# Power.net
KiCad netlist of a schematic drawn in Altium Designer
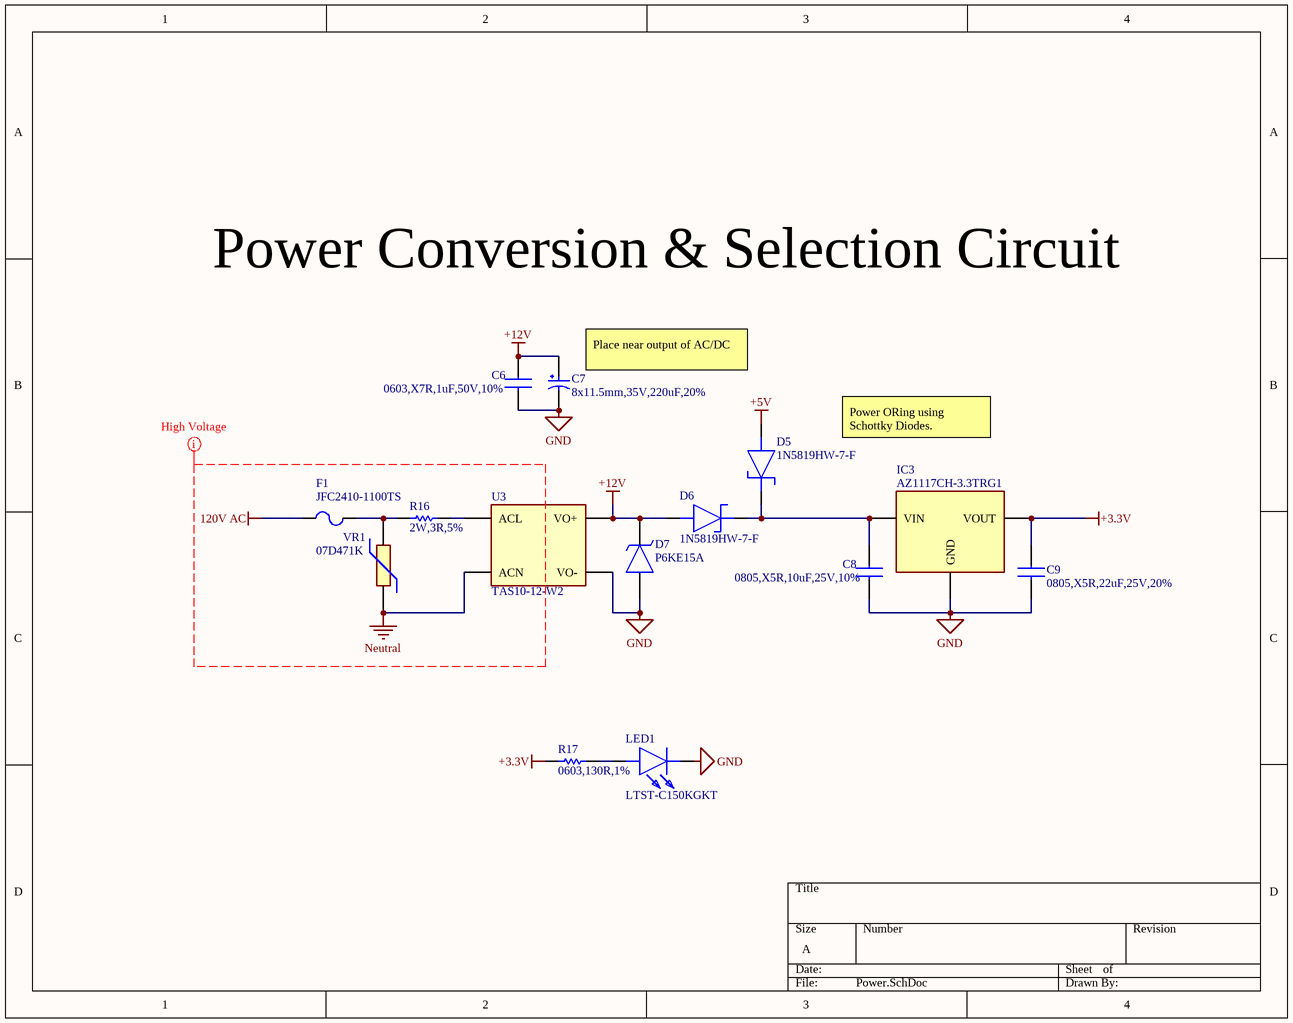
[diagram p0: Power.SchDoc]

(export (version "E")
  (design (tool "Eeschema 10.0.6"))
  (components
    (comp (ref "C6")
      (value "0603,X7R,1uF,50V,10%")
      (footprint "CAPC1608X90N")
      (description "50V 1uF X7R ±10% 0603 Multilayer Ceramic Capacitors MLCC - SMD/SMT ROHS")
      (fields
        (field (name "MANUFACTURER_PART_NUMBER") "CC0603KRX7R9BB105")
        (field (name "MOUSER PART NUMBER") "603-CC603KRX7R9BB105")
      )
      (libsource (lib "LC-SchLib") (part "CC0603KRX7R9BB105"))
    )
    (comp (ref "C7")
      (value "8x11.5mm,35V,220uF,20%")
      (footprint "CAPPRD350W60D825H1350")
      (fields
        (field (name "MANUFACTURER_PART_NUMBER") "35ZLH220MEFC8X11.5")
        (field (name "MOUSER PART NUMBER") "232-35ZLH220MEFC8X15")
        (field (name "LCSC PART NUMBER") "C107639")
      )
      (libsource (lib "LC-SchLib") (part "35ZLH220MEFC8X11.5"))
    )
    (comp (ref "C8")
      (value "0805,X5R,10uF,25V,10%")
      (footprint "CAPC2012X145N")
      (description "10 µF ±10% 25V Ceramic Capacitor X5R 0805 (2012 Metric)")
      (fields
        (field (name "MANUFACTURER_PART_NUMBER") "CC0805KKX5R8BB106")
        (field (name "MOUSER PART NUMBER") "603-CC805KKX5R8BB106")
      )
      (libsource (lib "LC-SchLib") (part "CC0805KKX5R8BB106"))
    )
    (comp (ref "C9")
      (value "0805,X5R,22uF,25V,20%")
      (footprint "CAPC2012X145N")
      (description "22 µF ±20% 25V Ceramic Capacitor X5R 0805 (2012 Metric)")
      (fields
        (field (name "MANUFACTURER_PART_NUMBER") "CC0805MKX5R8BB226")
        (field (name "MOUSER PART NUMBER") "603-CC805MKX5R8BB226")
      )
      (libsource (lib "LC-SchLib") (part "CC0805MKX5R8BB226"))
    )
    (comp (ref "D5")
      (value "1N5819HW-7-F")
      (footprint "SOD3716X145N")
      (description "40V 450mV@1A 1A SOD-123 Schottky Diodes ROHS")
      (fields (field (name "MOUSER PART NUMBER") "621-1N5819HW-F") (field (name "LCSC PART NUMBER") "C82544"))
      (libsource (lib "LC-SchLib") (part "1N5819HW-7-F"))
    )
    (comp (ref "D6")
      (value "1N5819HW-7-F")
      (footprint "SOD3716X145N")
      (description "40V 450mV@1A 1A SOD-123 Schottky Diodes ROHS")
      (fields (field (name "MOUSER PART NUMBER") "621-1N5819HW-F") (field (name "LCSC PART NUMBER") "C82544"))
      (libsource (lib "LC-SchLib") (part "1N5819HW-7-F"))
    )
    (comp (ref "D7")
      (value "P6KE15A")
      (footprint "DIOAD1936W88L640D324")
      (fields (field (name "MOUSER PART NUMBER") "511-P6KE15A") (field (name "LCSC PART NUMBER") "C1974865"))
      (libsource (lib "LC-SchLib") (part "P6KE15A"))
    )
    (comp (ref "F1")
      (value "JFC2410-1100TS")
      (footprint "F2410")
      (description "50A Surface Mount Fuse 1A 250V 250V 2410 Disposable fuses ROHS")
      (fields (field (name "LCSC PART NUMBER") "C136380"))
      (libsource (lib "LC-SchLib") (part "JFC2410-1100TS"))
    )
    (comp (ref "IC3")
      (value "AZ1117CH-3.3TRG1")
      (footprint "SOT230P700X180-4N")
      (fields
        (field (name "MOUSER PART NUMBER") "621-AZ1117CH-3.3TRG1")
        (field (name "LCSC PART NUMBER") "C92102")
      )
      (libsource (lib "LC-SchLib") (part "AZ1117CH-3.3TRG1"))
    )
    (comp (ref "LED1")
      (value "LTST-C150KGKT")
      (footprint "LEDC3216X120N")
      (fields
        (field (name "MOUSER PART NUMBER") "859-LTST-C150KGKT")
        (field (name "LCSC PART NUMBER") "C125085")
      )
      (libsource (lib "LC-SchLib") (part "LTST-C150KGKT"))
    )
    (comp (ref "R16")
      (value "2W,3R,5%")
      (footprint "RES-TH_BD4.0-L11.5-P15.50-D0.7")
      (description "Metal Film Resistor 3Ω 2W ±5% Through Hole,D4.5xL11.5mm Through Hole Resistors ROHS")
      (fields (field (name "LCSC PART NUMBER") "C176580"))
      (libsource (lib "LC-SchLib") (part "MFR2WSJT-73-3R"))
    )
    (comp (ref "R17")
      (value "0603,130R,1%")
      (footprint "RESC1608X55N")
      (description "130 Ohms ±1% 0.1W, 1/10W Chip Resistor 0603 (1608 Metric) Moisture Resistant Thick Film")
      (fields
        (field (name "MANUFACTURER_PART_NUMBER") "RC0603FR-07130RL")
        (field (name "LCSC PART NUMBER") "C141677")
      )
      (libsource (lib "LC-SchLib") (part "RC0603FR-07130RL"))
    )
    (comp (ref "U3")
      (value "TAS10-12-W2")
      (footprint "PWRM-TH_TAS10-XX-W2")
      (description "12V 830mA 85VAC~265VAC 100V~370V 10W AC/DC-DC 85% Through Hole,25x39mm AC-DC Power Modules ROHS")
      (fields (field (name "LCSC PART NUMBER") "C2687656"))
      (libsource (lib "LC-SchLib") (part "TAS10-12-W2"))
    )
    (comp (ref "VR1")
      (value "07D471K")
      (footprint "RES-TH_L9.0-W6.2-P5.00-D0.7-S6.20")
      (description "775V 385V 300V 423V~517V Through Hole,P=5mm Varistors ROHS")
      (fields (field (name "LCSC PART NUMBER") "C28756"))
      (libsource (lib "LC-SchLib") (part "07D471K"))
    )
  )
  (nets
    (net (code "1") (name "+3.3V") (class "Default")
      (node (ref "C9") (pin "2") (pinfunction "2_2") (pintype "passive"))
      (node (ref "IC3") (pin "2") (pinfunction "OUTPUT_2") (pintype "passive"))
      (node (ref "IC3") (pin "4") (pinfunction "VOUT_4") (pintype "passive"))
      (node (ref "R17") (pin "2") (pinfunction "2_2") (pintype "passive"))
    )
    (net (code "2") (name "+5V") (class "Default")
      (node (ref "D5") (pin "2") (pinfunction "A_2") (pintype "passive"))
    )
    (net (code "3") (name "+12V") (class "Default")
      (node (ref "C6") (pin "2") (pinfunction "2_2") (pintype "passive"))
      (node (ref "C7") (pin "1") (pinfunction "+_1") (pintype "passive"))
      (node (ref "D6") (pin "2") (pinfunction "A_2") (pintype "passive"))
      (node (ref "D7") (pin "1") (pinfunction "K_1") (pintype "passive"))
      (node (ref "U3") (pin "6") (pinfunction "VO+_6") (pintype "passive"))
    )
    (net (code "4") (name "120V AC") (class "Default")
      (node (ref "F1") (pin "1") (pinfunction "1_1") (pintype "passive"))
    )
    (net (code "5") (name "GND") (class "Default")
      (node (ref "C6") (pin "1") (pinfunction "1_1") (pintype "passive"))
      (node (ref "C7") (pin "2") (pinfunction "-_2") (pintype "passive"))
      (node (ref "C8") (pin "1") (pinfunction "1_1") (pintype "passive"))
      (node (ref "C9") (pin "1") (pinfunction "1_1") (pintype "passive"))
      (node (ref "D7") (pin "2") (pinfunction "A_2") (pintype "passive"))
      (node (ref "IC3") (pin "1") (pinfunction "GND_1") (pintype "passive"))
      (node (ref "LED1") (pin "1") (pinfunction "K_1") (pintype "passive"))
      (node (ref "U3") (pin "4") (pinfunction "VO-_4") (pintype "passive"))
    )
    (net (code "6") (name "Net-(D5-K)") (class "Default")
      (node (ref "C8") (pin "2") (pinfunction "2_2") (pintype "passive"))
      (node (ref "D5") (pin "1") (pinfunction "K_1") (pintype "passive"))
      (node (ref "D6") (pin "1") (pinfunction "K_1") (pintype "passive"))
      (node (ref "IC3") (pin "3") (pinfunction "VIN_3") (pintype "passive"))
    )
    (net (code "7") (name "Net-(F1-Pad2)") (class "Default")
      (node (ref "F1") (pin "2") (pinfunction "2_2") (pintype "passive"))
      (node (ref "R16") (pin "1") (pinfunction "1_1") (pintype "passive"))
      (node (ref "VR1") (pin "2") (pinfunction "2_2") (pintype "passive"))
    )
    (net (code "8") (name "Net-(LED1-A)") (class "Default")
      (node (ref "LED1") (pin "2") (pinfunction "A_2") (pintype "passive"))
      (node (ref "R17") (pin "1") (pinfunction "1_1") (pintype "passive"))
    )
    (net (code "9") (name "Net-(U3-ACL)") (class "Default")
      (node (ref "R16") (pin "2") (pinfunction "2_2") (pintype "passive"))
      (node (ref "U3") (pin "2") (pinfunction "ACL_2") (pintype "passive"))
    )
    (net (code "10") (name "Neutral") (class "Default")
      (node (ref "U3") (pin "1") (pinfunction "ACN_1") (pintype "passive"))
      (node (ref "VR1") (pin "1") (pinfunction "1_1") (pintype "passive"))
    )
  )
)
